# DAC_GainOutputStage7.net
KiCad netlist of a schematic drawn in EAGLE
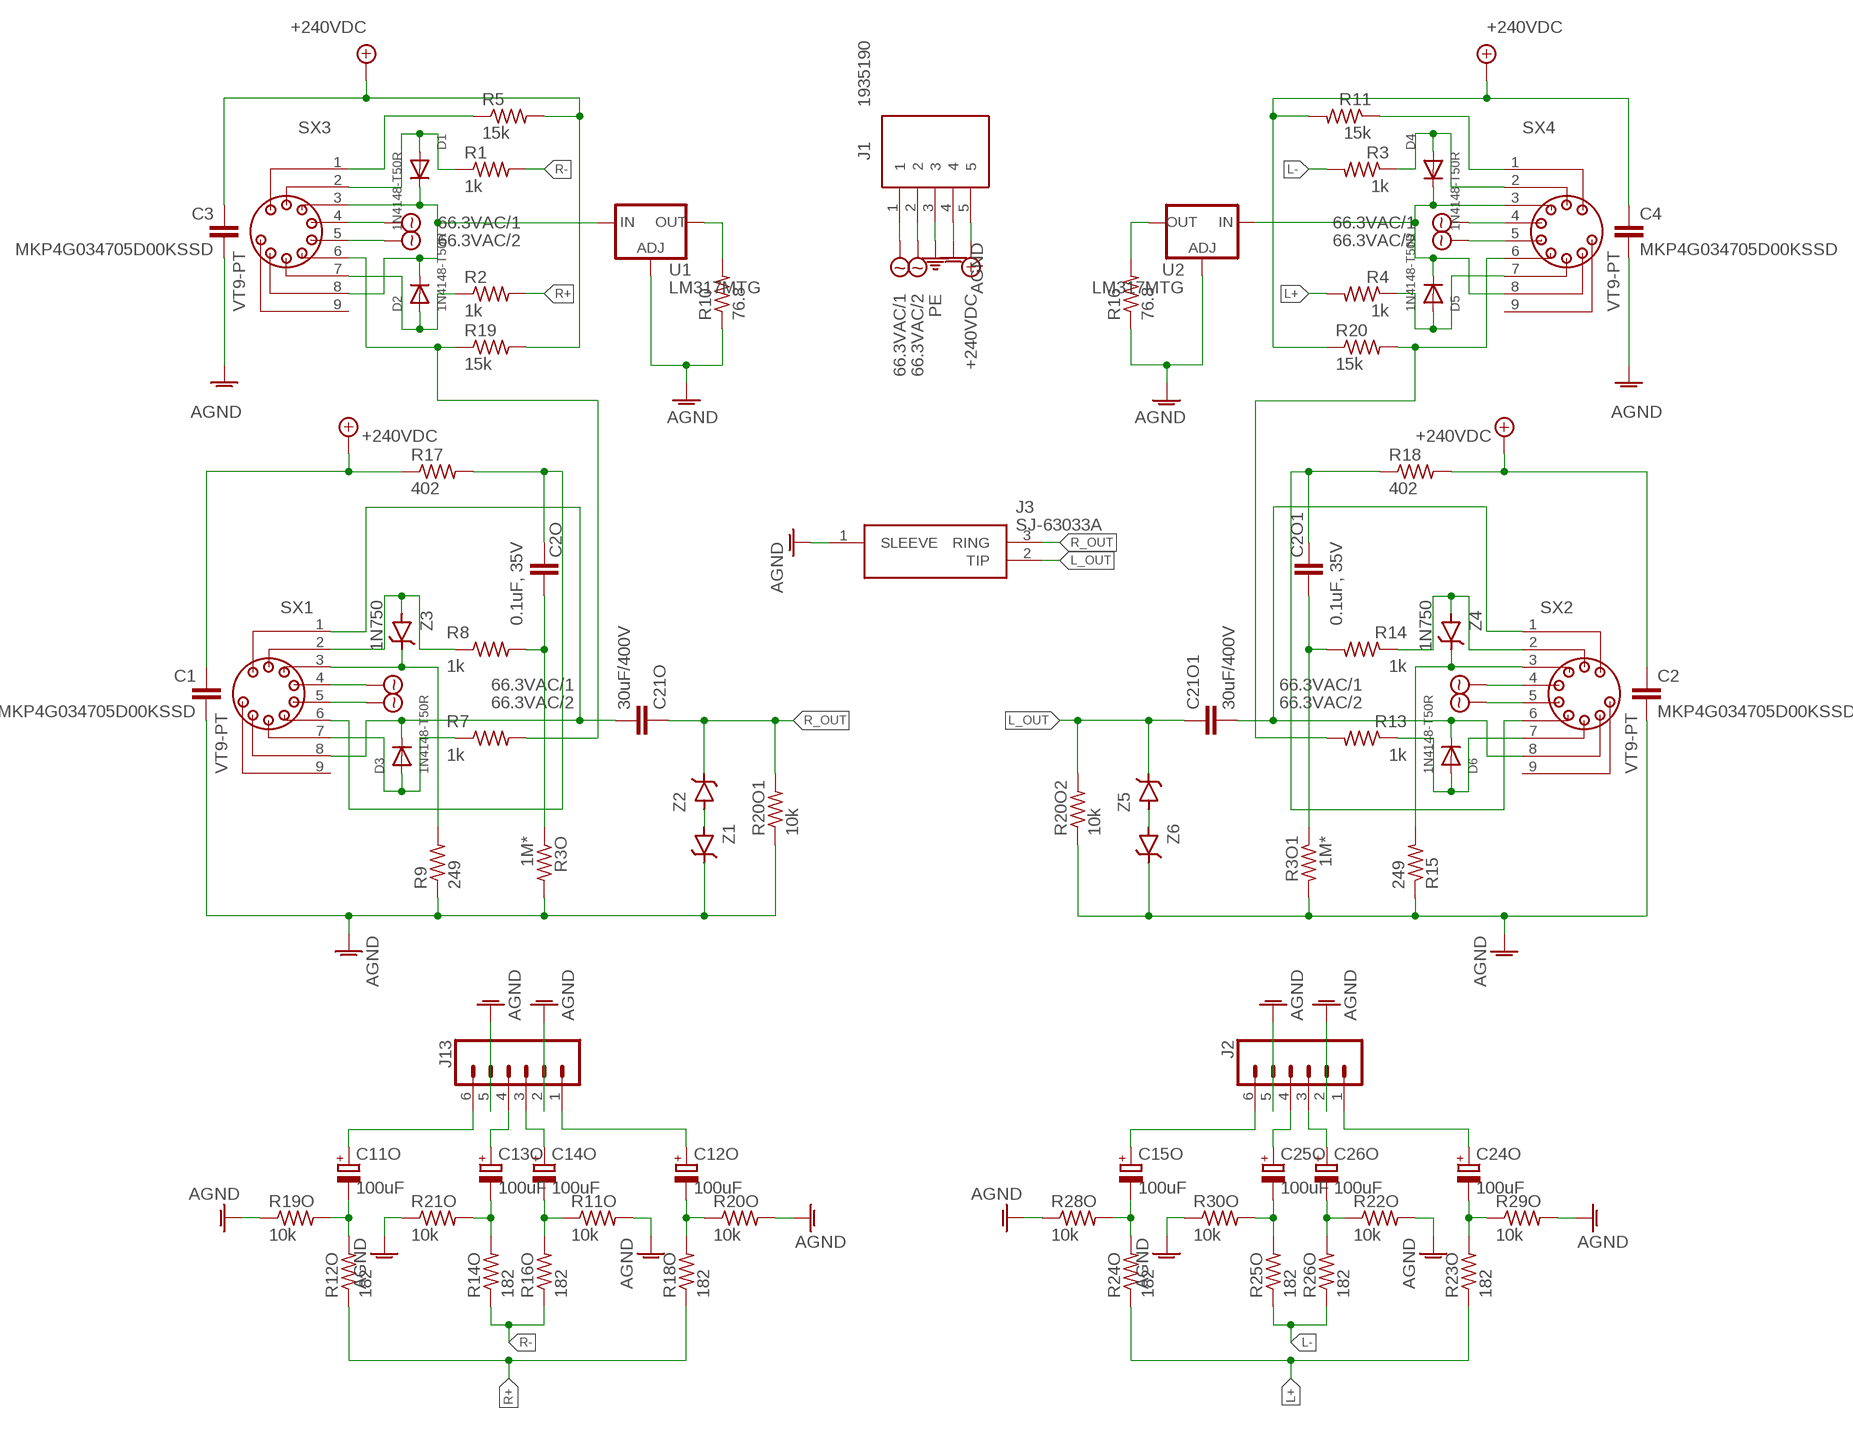
[diagram p0: schematic, sheet 1]

(export (version "E")
  (design (tool "Eeschema 10.0.6"))
  (components
    (comp (ref "C1")
      (value "MKP4G034705D00KSSD")
      (footprint "eagle-import:MKP4G034705D00KSSD")
      (fields (field (name "MOUSER_PART_NUMBER") "505-MKP4G034705DKSSD"))
      (libsource (lib "eagle-import") (part "MKP4G034705D00KSSD"))
    )
    (comp (ref "C2")
      (value "MKP4G034705D00KSSD")
      (footprint "eagle-import:MKP4G034705D00KSSD")
      (fields (field (name "MOUSER_PART_NUMBER") "505-MKP4G034705DKSSD"))
      (libsource (lib "eagle-import") (part "MKP4G034705D00KSSD"))
    )
    (comp (ref "C2O")
      (value "0.1uF, 35V")
      (footprint "eagle-import:MKS4B031002A00JC00")
      (fields
        (field (name "MANUFACTURER_PART_NUMBER") "MKS4B031002A00JC00")
        (field (name "MOUSER_PART_NUMBER") "505-MKS4B0312AJC")
      )
      (libsource (lib "eagle-import") (part "MKS4B031002A00JC00"))
    )
    (comp (ref "C2O1")
      (value "0.1uF, 35V")
      (footprint "eagle-import:MKS4B031002A00JC00")
      (fields
        (field (name "MANUFACTURER_PART_NUMBER") "MKS4B031002A00JC00")
        (field (name "MOUSER_PART_NUMBER") "505-MKS4B0312AJC")
      )
      (libsource (lib "eagle-import") (part "MKS4B031002A00JC00"))
    )
    (comp (ref "C3")
      (value "MKP4G034705D00KSSD")
      (footprint "eagle-import:MKP4G034705D00KSSD")
      (fields (field (name "MOUSER_PART_NUMBER") "505-MKP4G034705DKSSD"))
      (libsource (lib "eagle-import") (part "MKP4G034705D00KSSD"))
    )
    (comp (ref "C4")
      (value "MKP4G034705D00KSSD")
      (footprint "eagle-import:MKP4G034705D00KSSD")
      (fields (field (name "MOUSER_PART_NUMBER") "505-MKP4G034705DKSSD"))
      (libsource (lib "eagle-import") (part "MKP4G034705D00KSSD"))
    )
    (comp (ref "C11O")
      (value "100uF")
      (footprint "eagle-import:CAPPRD350W60D825H1300")
      (fields
        (field (name "ARROW_PART_NUMBER") "UFW1H101MPD1TD")
        (field (name "MOUSER_PART_NUMBER") "647-UFW1H101MPD1TD")
      )
      (libsource (lib "eagle-import") (part "UFW1H101MPD1TD"))
    )
    (comp (ref "C12O")
      (value "100uF")
      (footprint "eagle-import:CAPPRD350W60D825H1300")
      (fields
        (field (name "ARROW_PART_NUMBER") "UFW1H101MPD1TD")
        (field (name "MOUSER_PART_NUMBER") "647-UFW1H101MPD1TD")
      )
      (libsource (lib "eagle-import") (part "UFW1H101MPD1TD"))
    )
    (comp (ref "C13O")
      (value "100uF")
      (footprint "eagle-import:CAPPRD350W60D825H1300")
      (fields
        (field (name "ARROW_PART_NUMBER") "UFW1H101MPD1TD")
        (field (name "MOUSER_PART_NUMBER") "647-UFW1H101MPD1TD")
      )
      (libsource (lib "eagle-import") (part "UFW1H101MPD1TD"))
    )
    (comp (ref "C14O")
      (value "100uF")
      (footprint "eagle-import:CAPPRD350W60D825H1300")
      (fields
        (field (name "ARROW_PART_NUMBER") "UFW1H101MPD1TD")
        (field (name "MOUSER_PART_NUMBER") "647-UFW1H101MPD1TD")
      )
      (libsource (lib "eagle-import") (part "UFW1H101MPD1TD"))
    )
    (comp (ref "C15O")
      (value "100uF")
      (footprint "eagle-import:CAPPRD350W60D825H1300")
      (fields
        (field (name "ARROW_PART_NUMBER") "UFW1H101MPD1TD")
        (field (name "MOUSER_PART_NUMBER") "647-UFW1H101MPD1TD")
      )
      (libsource (lib "eagle-import") (part "UFW1H101MPD1TD"))
    )
    (comp (ref "C21O")
      (value "30uF/400V")
      (footprint "eagle-import:DCP4G053006ID2KSSD")
      (fields
        (field (name "MANUFACTURER_PART_NUMBER") "DCP4G053006ID2KSSD")
        (field (name "MOUSER_PART_NUMBER") "505-DCP4G0536ID2KSSD")
      )
      (libsource (lib "eagle-import") (part "DCP4G053006ID2KSSD"))
    )
    (comp (ref "C21O1")
      (value "30uF/400V")
      (footprint "eagle-import:DCP4G053006ID2KSSD")
      (fields
        (field (name "MANUFACTURER_PART_NUMBER") "DCP4G053006ID2KSSD")
        (field (name "MOUSER_PART_NUMBER") "505-DCP4G0536ID2KSSD")
      )
      (libsource (lib "eagle-import") (part "DCP4G053006ID2KSSD"))
    )
    (comp (ref "C24O")
      (value "100uF")
      (footprint "eagle-import:CAPPRD350W60D825H1300")
      (fields
        (field (name "ARROW_PART_NUMBER") "UFW1H101MPD1TD")
        (field (name "MOUSER_PART_NUMBER") "647-UFW1H101MPD1TD")
      )
      (libsource (lib "eagle-import") (part "UFW1H101MPD1TD"))
    )
    (comp (ref "C25O")
      (value "100uF")
      (footprint "eagle-import:CAPPRD350W60D825H1300")
      (fields
        (field (name "ARROW_PART_NUMBER") "UFW1H101MPD1TD")
        (field (name "MOUSER_PART_NUMBER") "647-UFW1H101MPD1TD")
      )
      (libsource (lib "eagle-import") (part "UFW1H101MPD1TD"))
    )
    (comp (ref "C26O")
      (value "100uF")
      (footprint "eagle-import:CAPPRD350W60D825H1300")
      (fields
        (field (name "ARROW_PART_NUMBER") "UFW1H101MPD1TD")
        (field (name "MOUSER_PART_NUMBER") "647-UFW1H101MPD1TD")
      )
      (libsource (lib "eagle-import") (part "UFW1H101MPD1TD"))
    )
    (comp (ref "D1")
      (value "1N4148-T50R")
      (footprint "eagle-import:DIOAD1068W53L380D172")
      (fields (field (name "MOUSER_PART_NUMBER") "512-1N4148T50R"))
      (libsource (lib "eagle-import") (part "1N4148-T50R"))
    )
    (comp (ref "D2")
      (value "1N4148-T50R")
      (footprint "eagle-import:DIOAD1068W53L380D172")
      (fields (field (name "MOUSER_PART_NUMBER") "512-1N4148T50R"))
      (libsource (lib "eagle-import") (part "1N4148-T50R"))
    )
    (comp (ref "D3")
      (value "1N4148-T50R")
      (footprint "eagle-import:DIOAD1068W53L380D172")
      (fields (field (name "MOUSER_PART_NUMBER") "512-1N4148T50R"))
      (libsource (lib "eagle-import") (part "1N4148-T50R"))
    )
    (comp (ref "D4")
      (value "1N4148-T50R")
      (footprint "eagle-import:DIOAD1068W53L380D172")
      (fields (field (name "MOUSER_PART_NUMBER") "512-1N4148T50R"))
      (libsource (lib "eagle-import") (part "1N4148-T50R"))
    )
    (comp (ref "D5")
      (value "1N4148-T50R")
      (footprint "eagle-import:DIOAD1068W53L380D172")
      (fields (field (name "MOUSER_PART_NUMBER") "512-1N4148T50R"))
      (libsource (lib "eagle-import") (part "1N4148-T50R"))
    )
    (comp (ref "D6")
      (value "1N4148-T50R")
      (footprint "eagle-import:DIOAD1068W53L380D172")
      (fields (field (name "MOUSER_PART_NUMBER") "512-1N4148T50R"))
      (libsource (lib "eagle-import") (part "1N4148-T50R"))
    )
    (comp (ref "J1")
      (value "1935190")
      (footprint "eagle-import:1935190")
      (fields (field (name "MOUSER_PART_NUMBER") "651-1935190"))
      (libsource (lib "eagle-import") (part "1935190"))
    )
    (comp (ref "J2")
      (value "CONN_06SILK_FEMALE_PTH")
      (footprint "eagle-import:1X06")
      (libsource (lib "eagle-import") (part "CONN_06SILK_FEMALE_PTH"))
    )
    (comp (ref "J3")
      (value "SJ-63033A")
      (footprint "eagle-import:SJ63033A")
      (libsource (lib "eagle-import") (part "SJ-63033A"))
    )
    (comp (ref "J13")
      (value "CONN_06SILK_FEMALE_PTH")
      (footprint "eagle-import:1X06")
      (libsource (lib "eagle-import") (part "CONN_06SILK_FEMALE_PTH"))
    )
    (comp (ref "R1")
      (value "1k")
      (footprint "eagle-import:0207_10")
      (fields
        (field (name "MANUFACTURER_PART_NUMBER") "LR1F1K0")
        (field (name "MOUSER_PART_NUMBER") "279-LR1F1K0")
      )
      (libsource (lib "eagle-import") (part "LR1F1K0"))
    )
    (comp (ref "R2")
      (value "1k")
      (footprint "eagle-import:0207_10")
      (fields
        (field (name "MANUFACTURER_PART_NUMBER") "LR1F1K0")
        (field (name "MOUSER_PART_NUMBER") "279-LR1F1K0")
      )
      (libsource (lib "eagle-import") (part "LR1F1K0"))
    )
    (comp (ref "R3")
      (value "1k")
      (footprint "eagle-import:0207_10")
      (fields
        (field (name "MANUFACTURER_PART_NUMBER") "LR1F1K0")
        (field (name "MOUSER_PART_NUMBER") "279-LR1F1K0")
      )
      (libsource (lib "eagle-import") (part "LR1F1K0"))
    )
    (comp (ref "R3O")
      (value "1M*")
      (footprint "eagle-import:0207_10")
      (fields
        (field (name "MANUFACTURER_PART_NUMBER") "LR1F1M0")
        (field (name "MOUSER_PART_NUMBER") "279-LR1F1M0")
      )
      (libsource (lib "eagle-import") (part "LR1F1M0"))
    )
    (comp (ref "R3O1")
      (value "1M*")
      (footprint "eagle-import:0207_10")
      (fields
        (field (name "MANUFACTURER_PART_NUMBER") "LR1F1M0")
        (field (name "MOUSER_PART_NUMBER") "279-LR1F1M0")
      )
      (libsource (lib "eagle-import") (part "LR1F1M0"))
    )
    (comp (ref "R4")
      (value "1k")
      (footprint "eagle-import:0207_10")
      (fields
        (field (name "MANUFACTURER_PART_NUMBER") "LR1F1K0")
        (field (name "MOUSER_PART_NUMBER") "279-LR1F1K0")
      )
      (libsource (lib "eagle-import") (part "LR1F1K0"))
    )
    (comp (ref "R5")
      (value "15k")
      (footprint "eagle-import:0411_15")
      (fields
        (field (name "MANUFACTURER_PART_NUMBER") "CPF215K000FKE14")
        (field (name "MOUSER_PART_NUMBER") "71-CPF2-F-15K-E3")
      )
      (libsource (lib "eagle-import") (part "CPF215K000FKE14"))
    )
    (comp (ref "R7")
      (value "1k")
      (footprint "eagle-import:0207_10")
      (fields
        (field (name "MANUFACTURER_PART_NUMBER") "LR1F1K0")
        (field (name "MOUSER_PART_NUMBER") "279-LR1F1K0")
      )
      (libsource (lib "eagle-import") (part "LR1F1K0"))
    )
    (comp (ref "R8")
      (value "1k")
      (footprint "eagle-import:0207_10")
      (fields
        (field (name "MANUFACTURER_PART_NUMBER") "LR1F1K0")
        (field (name "MOUSER_PART_NUMBER") "279-LR1F1K0")
      )
      (libsource (lib "eagle-import") (part "LR1F1K0"))
    )
    (comp (ref "R9")
      (value "249")
      (footprint "eagle-import:0207_10")
      (fields (field (name "MANUFACTURER_PART_NUMBER") "MBB02070C2490FRP00"))
      (libsource (lib "eagle-import") (part "MBB02070C2490FRP00"))
    )
    (comp (ref "R10")
      (value "76.8")
      (footprint "eagle-import:0207_10")
      (fields (field (name "MANUFACTURER_PART_NUMBER") "YR1B76R8CC"))
      (libsource (lib "eagle-import") (part "YR1B76R8CC"))
    )
    (comp (ref "R11")
      (value "15k")
      (footprint "eagle-import:0411_15")
      (fields
        (field (name "MANUFACTURER_PART_NUMBER") "CPF215K000FKE14")
        (field (name "MOUSER_PART_NUMBER") "71-CPF2-F-15K-E3")
      )
      (libsource (lib "eagle-import") (part "CPF215K000FKE14"))
    )
    (comp (ref "R11O")
      (value "10k")
      (footprint "eagle-import:0207_10")
      (fields
        (field (name "MANUFACTURER_PART_NUMBER") "LR1F10K")
        (field (name "MOUSER_PART_NUMBER") "279-LR1F10K")
      )
      (libsource (lib "eagle-import") (part "LR1F10K"))
    )
    (comp (ref "R12O")
      (value "182")
      (footprint "eagle-import:0207_10")
      (fields
        (field (name "MANUFACTURER") "Yageo")
        (field (name "MANUFACTURER_PART_NUMBER") "MF0207FTE52-182R")
        (field (name "MOUSER_PART_NUMBER") "603-MF0207FTE52-182R")
      )
      (libsource (lib "eagle-import") (part "MF0207FTE52-182R"))
    )
    (comp (ref "R13")
      (value "1k")
      (footprint "eagle-import:0207_10")
      (fields
        (field (name "MANUFACTURER_PART_NUMBER") "LR1F1K0")
        (field (name "MOUSER_PART_NUMBER") "279-LR1F1K0")
      )
      (libsource (lib "eagle-import") (part "LR1F1K0"))
    )
    (comp (ref "R14")
      (value "1k")
      (footprint "eagle-import:0207_10")
      (fields
        (field (name "MANUFACTURER_PART_NUMBER") "LR1F1K0")
        (field (name "MOUSER_PART_NUMBER") "279-LR1F1K0")
      )
      (libsource (lib "eagle-import") (part "LR1F1K0"))
    )
    (comp (ref "R14O")
      (value "182")
      (footprint "eagle-import:0207_10")
      (fields
        (field (name "MANUFACTURER") "Yageo")
        (field (name "MANUFACTURER_PART_NUMBER") "MF0207FTE52-182R")
        (field (name "MOUSER_PART_NUMBER") "603-MF0207FTE52-182R")
      )
      (libsource (lib "eagle-import") (part "MF0207FTE52-182R"))
    )
    (comp (ref "R15")
      (value "249")
      (footprint "eagle-import:0207_10")
      (fields (field (name "MANUFACTURER_PART_NUMBER") "MBB02070C2490FRP00"))
      (libsource (lib "eagle-import") (part "MBB02070C2490FRP00"))
    )
    (comp (ref "R16")
      (value "76.8")
      (footprint "eagle-import:0207_10")
      (fields (field (name "MANUFACTURER_PART_NUMBER") "YR1B76R8CC"))
      (libsource (lib "eagle-import") (part "YR1B76R8CC"))
    )
    (comp (ref "R16O")
      (value "182")
      (footprint "eagle-import:0207_10")
      (fields
        (field (name "MANUFACTURER") "Yageo")
        (field (name "MANUFACTURER_PART_NUMBER") "MF0207FTE52-182R")
        (field (name "MOUSER_PART_NUMBER") "603-MF0207FTE52-182R")
      )
      (libsource (lib "eagle-import") (part "MF0207FTE52-182R"))
    )
    (comp (ref "R17")
      (value "402")
      (footprint "eagle-import:0617_22")
      (fields (field (name "MANUFACTURER_PART_NUMBER") "RWR80S4020FRB12"))
      (libsource (lib "eagle-import") (part "RWR80S4020FRB12"))
    )
    (comp (ref "R18")
      (value "402")
      (footprint "eagle-import:0617_22")
      (fields (field (name "MANUFACTURER_PART_NUMBER") "RWR80S4020FRB12"))
      (libsource (lib "eagle-import") (part "RWR80S4020FRB12"))
    )
    (comp (ref "R18O")
      (value "182")
      (footprint "eagle-import:0207_10")
      (fields
        (field (name "MANUFACTURER") "Yageo")
        (field (name "MANUFACTURER_PART_NUMBER") "MF0207FTE52-182R")
        (field (name "MOUSER_PART_NUMBER") "603-MF0207FTE52-182R")
      )
      (libsource (lib "eagle-import") (part "MF0207FTE52-182R"))
    )
    (comp (ref "R19")
      (value "15k")
      (footprint "eagle-import:0411_15")
      (fields
        (field (name "MANUFACTURER_PART_NUMBER") "CPF215K000FKE14")
        (field (name "MOUSER_PART_NUMBER") "71-CPF2-F-15K-E3")
      )
      (libsource (lib "eagle-import") (part "CPF215K000FKE14"))
    )
    (comp (ref "R19O")
      (value "10k")
      (footprint "eagle-import:0207_10")
      (fields
        (field (name "MANUFACTURER_PART_NUMBER") "LR1F10K")
        (field (name "MOUSER_PART_NUMBER") "279-LR1F10K")
      )
      (libsource (lib "eagle-import") (part "LR1F10K"))
    )
    (comp (ref "R20")
      (value "15k")
      (footprint "eagle-import:0411_15")
      (fields
        (field (name "MANUFACTURER_PART_NUMBER") "CPF215K000FKE14")
        (field (name "MOUSER_PART_NUMBER") "71-CPF2-F-15K-E3")
      )
      (libsource (lib "eagle-import") (part "CPF215K000FKE14"))
    )
    (comp (ref "R20O")
      (value "10k")
      (footprint "eagle-import:0207_10")
      (fields
        (field (name "MANUFACTURER_PART_NUMBER") "LR1F10K")
        (field (name "MOUSER_PART_NUMBER") "279-LR1F10K")
      )
      (libsource (lib "eagle-import") (part "LR1F10K"))
    )
    (comp (ref "R20O1")
      (value "10k")
      (footprint "eagle-import:0207_10")
      (fields
        (field (name "MANUFACTURER_PART_NUMBER") "LR1F10K")
        (field (name "MOUSER_PART_NUMBER") "279-LR1F10K")
      )
      (libsource (lib "eagle-import") (part "LR1F10K"))
    )
    (comp (ref "R20O2")
      (value "10k")
      (footprint "eagle-import:0207_10")
      (fields
        (field (name "MANUFACTURER_PART_NUMBER") "LR1F10K")
        (field (name "MOUSER_PART_NUMBER") "279-LR1F10K")
      )
      (libsource (lib "eagle-import") (part "LR1F10K"))
    )
    (comp (ref "R21O")
      (value "10k")
      (footprint "eagle-import:0207_10")
      (fields
        (field (name "MANUFACTURER_PART_NUMBER") "LR1F10K")
        (field (name "MOUSER_PART_NUMBER") "279-LR1F10K")
      )
      (libsource (lib "eagle-import") (part "LR1F10K"))
    )
    (comp (ref "R22O")
      (value "10k")
      (footprint "eagle-import:0207_10")
      (fields
        (field (name "MANUFACTURER_PART_NUMBER") "LR1F10K")
        (field (name "MOUSER_PART_NUMBER") "279-LR1F10K")
      )
      (libsource (lib "eagle-import") (part "LR1F10K"))
    )
    (comp (ref "R23O")
      (value "182")
      (footprint "eagle-import:0207_10")
      (fields
        (field (name "MANUFACTURER") "Yageo")
        (field (name "MANUFACTURER_PART_NUMBER") "MF0207FTE52-182R")
        (field (name "MOUSER_PART_NUMBER") "603-MF0207FTE52-182R")
      )
      (libsource (lib "eagle-import") (part "MF0207FTE52-182R"))
    )
    (comp (ref "R24O")
      (value "182")
      (footprint "eagle-import:0207_10")
      (fields
        (field (name "MANUFACTURER") "Yageo")
        (field (name "MANUFACTURER_PART_NUMBER") "MF0207FTE52-182R")
        (field (name "MOUSER_PART_NUMBER") "603-MF0207FTE52-182R")
      )
      (libsource (lib "eagle-import") (part "MF0207FTE52-182R"))
    )
    (comp (ref "R25O")
      (value "182")
      (footprint "eagle-import:0207_10")
      (fields
        (field (name "MANUFACTURER") "Yageo")
        (field (name "MANUFACTURER_PART_NUMBER") "MF0207FTE52-182R")
        (field (name "MOUSER_PART_NUMBER") "603-MF0207FTE52-182R")
      )
      (libsource (lib "eagle-import") (part "MF0207FTE52-182R"))
    )
    (comp (ref "R26O")
      (value "182")
      (footprint "eagle-import:0207_10")
      (fields
        (field (name "MANUFACTURER") "Yageo")
        (field (name "MANUFACTURER_PART_NUMBER") "MF0207FTE52-182R")
        (field (name "MOUSER_PART_NUMBER") "603-MF0207FTE52-182R")
      )
      (libsource (lib "eagle-import") (part "MF0207FTE52-182R"))
    )
    (comp (ref "R28O")
      (value "10k")
      (footprint "eagle-import:0207_10")
      (fields
        (field (name "MANUFACTURER_PART_NUMBER") "LR1F10K")
        (field (name "MOUSER_PART_NUMBER") "279-LR1F10K")
      )
      (libsource (lib "eagle-import") (part "LR1F10K"))
    )
    (comp (ref "R29O")
      (value "10k")
      (footprint "eagle-import:0207_10")
      (fields
        (field (name "MANUFACTURER_PART_NUMBER") "LR1F10K")
        (field (name "MOUSER_PART_NUMBER") "279-LR1F10K")
      )
      (libsource (lib "eagle-import") (part "LR1F10K"))
    )
    (comp (ref "R30O")
      (value "10k")
      (footprint "eagle-import:0207_10")
      (fields
        (field (name "MANUFACTURER_PART_NUMBER") "LR1F10K")
        (field (name "MOUSER_PART_NUMBER") "279-LR1F10K")
      )
      (libsource (lib "eagle-import") (part "LR1F10K"))
    )
    (comp (ref "SX1")
      (value "VT9-PT")
      (footprint "eagle-import:VT9-PT")
      (libsource (lib "eagle-import") (part "VT9-PT"))
    )
    (comp (ref "SX2")
      (value "VT9-PT")
      (footprint "eagle-import:VT9-PT")
      (libsource (lib "eagle-import") (part "VT9-PT"))
    )
    (comp (ref "SX3")
      (value "VT9-PT")
      (footprint "eagle-import:VT9-PT")
      (libsource (lib "eagle-import") (part "VT9-PT"))
    )
    (comp (ref "SX4")
      (value "VT9-PT")
      (footprint "eagle-import:VT9-PT")
      (libsource (lib "eagle-import") (part "VT9-PT"))
    )
    (comp (ref "U1")
      (value "LM317MTG")
      (footprint "eagle-import:TO254P482X997X2018-3P")
      (fields (field (name "MOUSER_PART_NUMBER") "863-LM317MTG"))
      (libsource (lib "eagle-import") (part "LM317MTG"))
    )
    (comp (ref "U2")
      (value "LM317MTG")
      (footprint "eagle-import:TO254P482X997X2018-3P")
      (fields (field (name "MOUSER_PART_NUMBER") "863-LM317MTG"))
      (libsource (lib "eagle-import") (part "LM317MTG"))
    )
    (comp (ref "Z1")
      (value "BZX79-C16,113")
      (footprint "eagle-import:DIOAD1165W56L425D185")
      (libsource (lib "eagle-import") (part "BZX79-C16,113"))
    )
    (comp (ref "Z2")
      (value "BZX79-C16,113")
      (footprint "eagle-import:DIOAD1165W56L425D185")
      (libsource (lib "eagle-import") (part "BZX79-C16,113"))
    )
    (comp (ref "Z3")
      (value "1N750")
      (footprint "eagle-import:DIOAD1256W56L444D203")
      (fields (field (name "MOUSER_PART_NUMBER") "494-1N750(DO-35)"))
      (libsource (lib "eagle-import") (part "1N750"))
    )
    (comp (ref "Z4")
      (value "1N750")
      (footprint "eagle-import:DIOAD1256W56L444D203")
      (fields (field (name "MOUSER_PART_NUMBER") "494-1N750(DO-35)"))
      (libsource (lib "eagle-import") (part "1N750"))
    )
    (comp (ref "Z5")
      (value "BZX79-C16,113")
      (footprint "eagle-import:DIOAD1165W56L425D185")
      (libsource (lib "eagle-import") (part "BZX79-C16,113"))
    )
    (comp (ref "Z6")
      (value "BZX79-C16,113")
      (footprint "eagle-import:DIOAD1165W56L425D185")
      (libsource (lib "eagle-import") (part "BZX79-C16,113"))
    )
  )
  (nets
    (net (code "1") (name "+240VDC") (class "Default")
      (node (ref "C1") (pin "1") (pinfunction "1_1") (pintype "passive"))
      (node (ref "C2") (pin "1") (pinfunction "1_1") (pintype "passive"))
      (node (ref "C3") (pin "1") (pinfunction "1_1") (pintype "passive"))
      (node (ref "C4") (pin "1") (pinfunction "1_1") (pintype "passive"))
      (node (ref "J1") (pin "5") (pinfunction "5_5") (pintype "bidirectional"))
      (node (ref "R11") (pin "2") (pinfunction "2_2") (pintype "passive"))
      (node (ref "R17") (pin "1") (pinfunction "1_1") (pintype "passive"))
      (node (ref "R18") (pin "2") (pinfunction "2_2") (pintype "passive"))
      (node (ref "R19") (pin "2") (pinfunction "2_2") (pintype "passive"))
      (node (ref "R20") (pin "1") (pinfunction "1_1") (pintype "passive"))
      (node (ref "R5") (pin "2") (pinfunction "2_2") (pintype "passive"))
    )
    (net (code "2") (name "66.3VAC{slash}1") (class "Default")
      (node (ref "J1") (pin "1") (pinfunction "1_1") (pintype "bidirectional"))
      (node (ref "SX1") (pin "4") (pinfunction "4_4") (pintype "passive"))
      (node (ref "SX2") (pin "4") (pinfunction "4_4") (pintype "passive"))
      (node (ref "SX3") (pin "4") (pinfunction "4_4") (pintype "passive"))
      (node (ref "SX4") (pin "4") (pinfunction "4_4") (pintype "passive"))
    )
    (net (code "3") (name "66.3VAC{slash}2") (class "Default")
      (node (ref "J1") (pin "2") (pinfunction "2_2") (pintype "bidirectional"))
      (node (ref "SX1") (pin "5") (pinfunction "5_5") (pintype "passive"))
      (node (ref "SX2") (pin "5") (pinfunction "5_5") (pintype "passive"))
      (node (ref "SX3") (pin "5") (pinfunction "5_5") (pintype "passive"))
      (node (ref "SX4") (pin "5") (pinfunction "5_5") (pintype "passive"))
    )
    (net (code "4") (name "AGND") (class "Default")
      (node (ref "C1") (pin "2") (pinfunction "2_2") (pintype "passive"))
      (node (ref "C2") (pin "2") (pinfunction "2_2") (pintype "passive"))
      (node (ref "C3") (pin "2") (pinfunction "2_2") (pintype "passive"))
      (node (ref "C4") (pin "2") (pinfunction "2_2") (pintype "passive"))
      (node (ref "J1") (pin "4") (pinfunction "4_4") (pintype "bidirectional"))
      (node (ref "J13") (pin "2") (pinfunction "2_2") (pintype "passive"))
      (node (ref "J13") (pin "5") (pinfunction "5_5") (pintype "passive"))
      (node (ref "J2") (pin "2") (pinfunction "2_2") (pintype "passive"))
      (node (ref "J2") (pin "5") (pinfunction "5_5") (pintype "passive"))
      (node (ref "J3") (pin "1") (pinfunction "SLEEVE_1") (pintype "bidirectional"))
      (node (ref "R10") (pin "1") (pinfunction "1_1") (pintype "passive"))
      (node (ref "R11O") (pin "2") (pinfunction "2_2") (pintype "passive"))
      (node (ref "R15") (pin "1") (pinfunction "1_1") (pintype "passive"))
      (node (ref "R16") (pin "1") (pinfunction "1_1") (pintype "passive"))
      (node (ref "R19O") (pin "1") (pinfunction "1_1") (pintype "passive"))
      (node (ref "R20O") (pin "2") (pinfunction "2_2") (pintype "passive"))
      (node (ref "R20O1") (pin "1") (pinfunction "1_1") (pintype "passive"))
      (node (ref "R20O2") (pin "1") (pinfunction "1_1") (pintype "passive"))
      (node (ref "R21O") (pin "1") (pinfunction "1_1") (pintype "passive"))
      (node (ref "R22O") (pin "2") (pinfunction "2_2") (pintype "passive"))
      (node (ref "R28O") (pin "1") (pinfunction "1_1") (pintype "passive"))
      (node (ref "R29O") (pin "2") (pinfunction "2_2") (pintype "passive"))
      (node (ref "R30O") (pin "1") (pinfunction "1_1") (pintype "passive"))
      (node (ref "R3O") (pin "2") (pinfunction "2_2") (pintype "passive"))
      (node (ref "R3O1") (pin "2") (pinfunction "2_2") (pintype "passive"))
      (node (ref "R9") (pin "1") (pinfunction "1_1") (pintype "passive"))
      (node (ref "U1") (pin "1") (pinfunction "ADJ_1") (pintype "input"))
      (node (ref "U2") (pin "1") (pinfunction "ADJ_1") (pintype "input"))
      (node (ref "Z1") (pin "1") (pinfunction "C_1") (pintype "passive"))
      (node (ref "Z6") (pin "1") (pinfunction "C_1") (pintype "passive"))
    )
    (net (code "5") (name "L+") (class "Default")
      (node (ref "R23O") (pin "1") (pinfunction "1_1") (pintype "passive"))
      (node (ref "R24O") (pin "1") (pinfunction "1_1") (pintype "passive"))
      (node (ref "R4") (pin "2") (pinfunction "2_2") (pintype "passive"))
    )
    (net (code "6") (name "L-") (class "Default")
      (node (ref "R25O") (pin "1") (pinfunction "1_1") (pintype "passive"))
      (node (ref "R26O") (pin "1") (pinfunction "1_1") (pintype "passive"))
      (node (ref "R3") (pin "2") (pinfunction "2_2") (pintype "passive"))
    )
    (net (code "7") (name "L_OUT") (class "Default")
      (node (ref "C21O1") (pin "1") (pinfunction "1_1") (pintype "passive"))
      (node (ref "J3") (pin "2") (pinfunction "TIP_2") (pintype "bidirectional"))
      (node (ref "R20O2") (pin "2") (pinfunction "2_2") (pintype "passive"))
      (node (ref "Z5") (pin "1") (pinfunction "C_1") (pintype "passive"))
    )
    (net (code "8") (name "Net-(C2O-Pad1)") (class "Default")
      (node (ref "C2O") (pin "1") (pinfunction "1_1") (pintype "passive"))
      (node (ref "R17") (pin "2") (pinfunction "2_2") (pintype "passive"))
      (node (ref "SX1") (pin "6") (pinfunction "6_6") (pintype "passive"))
    )
    (net (code "9") (name "Net-(C2O-Pad2)") (class "Default")
      (node (ref "C2O") (pin "2") (pinfunction "2_2") (pintype "passive"))
      (node (ref "R3O") (pin "1") (pinfunction "1_1") (pintype "passive"))
      (node (ref "R8") (pin "2") (pinfunction "2_2") (pintype "passive"))
    )
    (net (code "10") (name "Net-(C2O1-Pad1)") (class "Default")
      (node (ref "C2O1") (pin "1") (pinfunction "1_1") (pintype "passive"))
      (node (ref "R18") (pin "1") (pinfunction "1_1") (pintype "passive"))
      (node (ref "SX2") (pin "6") (pinfunction "6_6") (pintype "passive"))
    )
    (net (code "11") (name "Net-(C2O1-Pad2)") (class "Default")
      (node (ref "C2O1") (pin "2") (pinfunction "2_2") (pintype "passive"))
      (node (ref "R14") (pin "2") (pinfunction "2_2") (pintype "passive"))
      (node (ref "R3O1") (pin "1") (pinfunction "1_1") (pintype "passive"))
    )
    (net (code "12") (name "Net-(C11O-+)") (class "Default")
      (node (ref "C11O") (pin "1") (pinfunction "+_1") (pintype "passive"))
      (node (ref "J13") (pin "6") (pinfunction "6_6") (pintype "passive"))
    )
    (net (code "13") (name "Net-(C11O--)") (class "Default")
      (node (ref "C11O") (pin "2") (pinfunction "-_2") (pintype "passive"))
      (node (ref "R12O") (pin "2") (pinfunction "2_2") (pintype "passive"))
      (node (ref "R19O") (pin "2") (pinfunction "2_2") (pintype "passive"))
    )
    (net (code "14") (name "Net-(C12O-+)") (class "Default")
      (node (ref "C12O") (pin "1") (pinfunction "+_1") (pintype "passive"))
      (node (ref "J13") (pin "1") (pinfunction "1_1") (pintype "passive"))
    )
    (net (code "15") (name "Net-(C12O--)") (class "Default")
      (node (ref "C12O") (pin "2") (pinfunction "-_2") (pintype "passive"))
      (node (ref "R18O") (pin "2") (pinfunction "2_2") (pintype "passive"))
      (node (ref "R20O") (pin "1") (pinfunction "1_1") (pintype "passive"))
    )
    (net (code "16") (name "Net-(C13O-+)") (class "Default")
      (node (ref "C13O") (pin "1") (pinfunction "+_1") (pintype "passive"))
      (node (ref "J13") (pin "4") (pinfunction "4_4") (pintype "passive"))
    )
    (net (code "17") (name "Net-(C13O--)") (class "Default")
      (node (ref "C13O") (pin "2") (pinfunction "-_2") (pintype "passive"))
      (node (ref "R14O") (pin "2") (pinfunction "2_2") (pintype "passive"))
      (node (ref "R21O") (pin "2") (pinfunction "2_2") (pintype "passive"))
    )
    (net (code "18") (name "Net-(C14O-+)") (class "Default")
      (node (ref "C14O") (pin "1") (pinfunction "+_1") (pintype "passive"))
      (node (ref "J13") (pin "3") (pinfunction "3_3") (pintype "passive"))
    )
    (net (code "19") (name "Net-(C14O--)") (class "Default")
      (node (ref "C14O") (pin "2") (pinfunction "-_2") (pintype "passive"))
      (node (ref "R11O") (pin "1") (pinfunction "1_1") (pintype "passive"))
      (node (ref "R16O") (pin "2") (pinfunction "2_2") (pintype "passive"))
    )
    (net (code "20") (name "Net-(C15O-+)") (class "Default")
      (node (ref "C15O") (pin "1") (pinfunction "+_1") (pintype "passive"))
      (node (ref "J2") (pin "6") (pinfunction "6_6") (pintype "passive"))
    )
    (net (code "21") (name "Net-(C15O--)") (class "Default")
      (node (ref "C15O") (pin "2") (pinfunction "-_2") (pintype "passive"))
      (node (ref "R24O") (pin "2") (pinfunction "2_2") (pintype "passive"))
      (node (ref "R28O") (pin "2") (pinfunction "2_2") (pintype "passive"))
    )
    (net (code "22") (name "Net-(C24O-+)") (class "Default")
      (node (ref "C24O") (pin "1") (pinfunction "+_1") (pintype "passive"))
      (node (ref "J2") (pin "1") (pinfunction "1_1") (pintype "passive"))
    )
    (net (code "23") (name "Net-(C24O--)") (class "Default")
      (node (ref "C24O") (pin "2") (pinfunction "-_2") (pintype "passive"))
      (node (ref "R23O") (pin "2") (pinfunction "2_2") (pintype "passive"))
      (node (ref "R29O") (pin "1") (pinfunction "1_1") (pintype "passive"))
    )
    (net (code "24") (name "Net-(C25O-+)") (class "Default")
      (node (ref "C25O") (pin "1") (pinfunction "+_1") (pintype "passive"))
      (node (ref "J2") (pin "4") (pinfunction "4_4") (pintype "passive"))
    )
    (net (code "25") (name "Net-(C25O--)") (class "Default")
      (node (ref "C25O") (pin "2") (pinfunction "-_2") (pintype "passive"))
      (node (ref "R25O") (pin "2") (pinfunction "2_2") (pintype "passive"))
      (node (ref "R30O") (pin "2") (pinfunction "2_2") (pintype "passive"))
    )
    (net (code "26") (name "Net-(C26O-+)") (class "Default")
      (node (ref "C26O") (pin "1") (pinfunction "+_1") (pintype "passive"))
      (node (ref "J2") (pin "3") (pinfunction "3_3") (pintype "passive"))
    )
    (net (code "27") (name "Net-(C26O--)") (class "Default")
      (node (ref "C26O") (pin "2") (pinfunction "-_2") (pintype "passive"))
      (node (ref "R22O") (pin "1") (pinfunction "1_1") (pintype "passive"))
      (node (ref "R26O") (pin "2") (pinfunction "2_2") (pintype "passive"))
    )
    (net (code "28") (name "Net-(D1-A)") (class "Default")
      (node (ref "D1") (pin "2") (pinfunction "A_2") (pintype "passive"))
      (node (ref "R1") (pin "1") (pinfunction "1_1") (pintype "passive"))
      (node (ref "SX3") (pin "2") (pinfunction "2_2") (pintype "passive"))
    )
    (net (code "29") (name "Net-(D1-C)") (class "Default")
      (node (ref "D1") (pin "1") (pinfunction "C_1") (pintype "passive"))
      (node (ref "D2") (pin "1") (pinfunction "C_1") (pintype "passive"))
      (node (ref "SX3") (pin "3") (pinfunction "3_3") (pintype "passive"))
      (node (ref "SX3") (pin "8") (pinfunction "8_8") (pintype "passive"))
      (node (ref "U1") (pin "3") (pinfunction "IN_3") (pintype "input"))
    )
    (net (code "30") (name "Net-(D2-A)") (class "Default")
      (node (ref "D2") (pin "2") (pinfunction "A_2") (pintype "passive"))
      (node (ref "R2") (pin "1") (pinfunction "1_1") (pintype "passive"))
      (node (ref "SX3") (pin "7") (pinfunction "7_7") (pintype "passive"))
    )
    (net (code "31") (name "Net-(D3-A)") (class "Default")
      (node (ref "D3") (pin "2") (pinfunction "A_2") (pintype "passive"))
      (node (ref "R7") (pin "1") (pinfunction "1_1") (pintype "passive"))
      (node (ref "SX1") (pin "7") (pinfunction "7_7") (pintype "passive"))
    )
    (net (code "32") (name "Net-(D3-C)") (class "Default")
      (node (ref "C21O") (pin "2") (pinfunction "2_2") (pintype "passive"))
      (node (ref "D3") (pin "1") (pinfunction "C_1") (pintype "passive"))
      (node (ref "SX1") (pin "1") (pinfunction "1_1") (pintype "passive"))
      (node (ref "SX1") (pin "8") (pinfunction "8_8") (pintype "passive"))
    )
    (net (code "33") (name "Net-(D4-A)") (class "Default")
      (node (ref "D4") (pin "2") (pinfunction "A_2") (pintype "passive"))
      (node (ref "R3") (pin "1") (pinfunction "1_1") (pintype "passive"))
      (node (ref "SX4") (pin "2") (pinfunction "2_2") (pintype "passive"))
    )
    (net (code "34") (name "Net-(D4-C)") (class "Default")
      (node (ref "D4") (pin "1") (pinfunction "C_1") (pintype "passive"))
      (node (ref "D5") (pin "1") (pinfunction "C_1") (pintype "passive"))
      (node (ref "SX4") (pin "3") (pinfunction "3_3") (pintype "passive"))
      (node (ref "SX4") (pin "8") (pinfunction "8_8") (pintype "passive"))
      (node (ref "U2") (pin "3") (pinfunction "IN_3") (pintype "input"))
    )
    (net (code "35") (name "Net-(D5-A)") (class "Default")
      (node (ref "D5") (pin "2") (pinfunction "A_2") (pintype "passive"))
      (node (ref "R4") (pin "1") (pinfunction "1_1") (pintype "passive"))
      (node (ref "SX4") (pin "7") (pinfunction "7_7") (pintype "passive"))
    )
    (net (code "36") (name "Net-(D6-A)") (class "Default")
      (node (ref "D6") (pin "2") (pinfunction "A_2") (pintype "passive"))
      (node (ref "R13") (pin "1") (pinfunction "1_1") (pintype "passive"))
      (node (ref "SX2") (pin "7") (pinfunction "7_7") (pintype "passive"))
    )
    (net (code "37") (name "Net-(D6-C)") (class "Default")
      (node (ref "C21O1") (pin "2") (pinfunction "2_2") (pintype "passive"))
      (node (ref "D6") (pin "1") (pinfunction "C_1") (pintype "passive"))
      (node (ref "SX2") (pin "1") (pinfunction "1_1") (pintype "passive"))
      (node (ref "SX2") (pin "8") (pinfunction "8_8") (pintype "passive"))
    )
    (net (code "38") (name "Net-(R5-Pad1)") (class "Default")
      (node (ref "R5") (pin "1") (pinfunction "1_1") (pintype "passive"))
      (node (ref "SX3") (pin "1") (pinfunction "1_1") (pintype "passive"))
    )
    (net (code "39") (name "Net-(R11-Pad1)") (class "Default")
      (node (ref "R11") (pin "1") (pinfunction "1_1") (pintype "passive"))
      (node (ref "SX4") (pin "1") (pinfunction "1_1") (pintype "passive"))
    )
    (net (code "40") (name "Net-(R13-Pad2)") (class "Default")
      (node (ref "R13") (pin "2") (pinfunction "2_2") (pintype "passive"))
      (node (ref "R20") (pin "2") (pinfunction "2_2") (pintype "passive"))
      (node (ref "SX4") (pin "6") (pinfunction "6_6") (pintype "passive"))
    )
    (net (code "41") (name "Net-(R19-Pad1)") (class "Default")
      (node (ref "R19") (pin "1") (pinfunction "1_1") (pintype "passive"))
      (node (ref "R7") (pin "2") (pinfunction "2_2") (pintype "passive"))
      (node (ref "SX3") (pin "6") (pinfunction "6_6") (pintype "passive"))
    )
    (net (code "42") (name "Net-(U1-OUT)") (class "Default")
      (node (ref "R10") (pin "2") (pinfunction "2_2") (pintype "passive"))
      (node (ref "U1") (pin "2") (pinfunction "OUT_2") (pintype "passive"))
    )
    (net (code "43") (name "Net-(U2-OUT)") (class "Default")
      (node (ref "R16") (pin "2") (pinfunction "2_2") (pintype "passive"))
      (node (ref "U2") (pin "2") (pinfunction "OUT_2") (pintype "passive"))
    )
    (net (code "44") (name "Net-(Z1-A)") (class "Default")
      (node (ref "Z1") (pin "2") (pinfunction "A_2") (pintype "passive"))
      (node (ref "Z2") (pin "2") (pinfunction "A_2") (pintype "passive"))
    )
    (net (code "45") (name "Net-(Z3-A)") (class "Default")
      (node (ref "R8") (pin "1") (pinfunction "1_1") (pintype "passive"))
      (node (ref "SX1") (pin "2") (pinfunction "2_2") (pintype "passive"))
      (node (ref "Z3") (pin "2") (pinfunction "A_2") (pintype "passive"))
    )
    (net (code "46") (name "Net-(Z3-C)") (class "Default")
      (node (ref "R9") (pin "2") (pinfunction "2_2") (pintype "passive"))
      (node (ref "SX1") (pin "3") (pinfunction "3_3") (pintype "passive"))
      (node (ref "Z3") (pin "1") (pinfunction "C_1") (pintype "passive"))
    )
    (net (code "47") (name "Net-(Z4-A)") (class "Default")
      (node (ref "R14") (pin "1") (pinfunction "1_1") (pintype "passive"))
      (node (ref "SX2") (pin "2") (pinfunction "2_2") (pintype "passive"))
      (node (ref "Z4") (pin "2") (pinfunction "A_2") (pintype "passive"))
    )
    (net (code "48") (name "Net-(Z4-C)") (class "Default")
      (node (ref "R15") (pin "2") (pinfunction "2_2") (pintype "passive"))
      (node (ref "SX2") (pin "3") (pinfunction "3_3") (pintype "passive"))
      (node (ref "Z4") (pin "1") (pinfunction "C_1") (pintype "passive"))
    )
    (net (code "49") (name "Net-(Z5-A)") (class "Default")
      (node (ref "Z5") (pin "2") (pinfunction "A_2") (pintype "passive"))
      (node (ref "Z6") (pin "2") (pinfunction "A_2") (pintype "passive"))
    )
    (net (code "50") (name "PE") (class "Default")
      (node (ref "J1") (pin "3") (pinfunction "3_3") (pintype "bidirectional"))
    )
    (net (code "51") (name "R+") (class "Default")
      (node (ref "R12O") (pin "1") (pinfunction "1_1") (pintype "passive"))
      (node (ref "R18O") (pin "1") (pinfunction "1_1") (pintype "passive"))
      (node (ref "R2") (pin "2") (pinfunction "2_2") (pintype "passive"))
    )
    (net (code "52") (name "R-") (class "Default")
      (node (ref "R1") (pin "2") (pinfunction "2_2") (pintype "passive"))
      (node (ref "R14O") (pin "1") (pinfunction "1_1") (pintype "passive"))
      (node (ref "R16O") (pin "1") (pinfunction "1_1") (pintype "passive"))
    )
    (net (code "53") (name "R_OUT") (class "Default")
      (node (ref "C21O") (pin "1") (pinfunction "1_1") (pintype "passive"))
      (node (ref "J3") (pin "3") (pinfunction "RING_3") (pintype "bidirectional"))
      (node (ref "R20O1") (pin "2") (pinfunction "2_2") (pintype "passive"))
      (node (ref "Z2") (pin "1") (pinfunction "C_1") (pintype "passive"))
    )
    (net (code "54") (name "unconnected-(SX1-Pad9)") (class "Default")
      (node (ref "SX1") (pin "9") (pinfunction "9_9") (pintype "passive"))
    )
    (net (code "55") (name "unconnected-(SX2-Pad9)") (class "Default")
      (node (ref "SX2") (pin "9") (pinfunction "9_9") (pintype "passive"))
    )
    (net (code "56") (name "unconnected-(SX3-Pad9)") (class "Default")
      (node (ref "SX3") (pin "9") (pinfunction "9_9") (pintype "passive"))
    )
    (net (code "57") (name "unconnected-(SX4-Pad9)") (class "Default")
      (node (ref "SX4") (pin "9") (pinfunction "9_9") (pintype "passive"))
    )
  )
)
